# firstProject_1_1.net
KiCad netlist of a schematic drawn in EAGLE
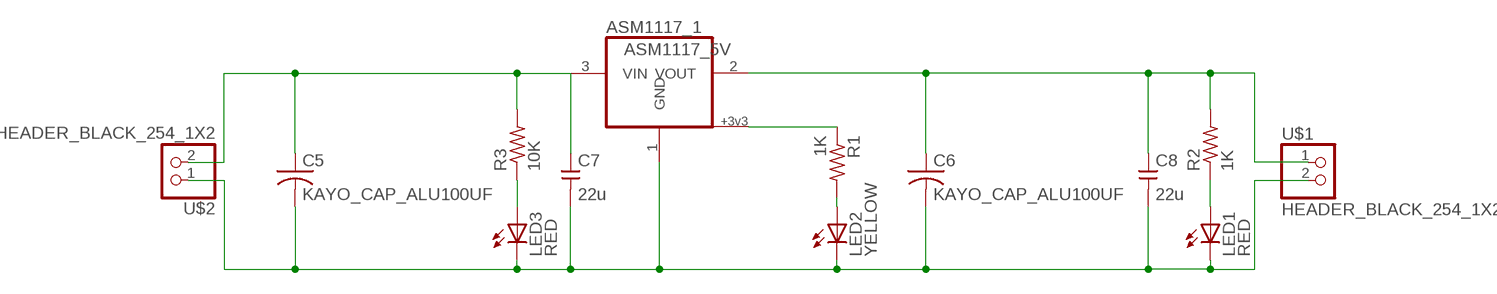
[diagram p0: schematic, sheet 1]

(export (version "E")
  (design (tool "Eeschema 10.0.6"))
  (components
    (comp (ref "ASM1117_1")
      (value "ASM1117_5V")
      (footprint "eagle-import:SOT223")
      (fields (field (name "MPN") "REG1117"))
      (libsource (lib "eagle-import") (part "KAYO_REG1117_SOT223_ASM1117_5V"))
    )
    (comp (ref "C5")
      (value "KAYO_CAP_ALU100UF")
      (footprint "eagle-import:RCL_PANASONIC_D")
      (libsource (lib "eagle-import") (part "KAYO_CAP_ALU100UF"))
    )
    (comp (ref "C6")
      (value "KAYO_CAP_ALU100UF")
      (footprint "eagle-import:RCL_PANASONIC_D")
      (libsource (lib "eagle-import") (part "KAYO_CAP_ALU100UF"))
    )
    (comp (ref "C7")
      (value "22u")
      (footprint "eagle-import:KXN_C0603")
      (libsource (lib "eagle-import") (part "KAYO_CAP_CERAMIC_KXN_060322UF"))
    )
    (comp (ref "C8")
      (value "22u")
      (footprint "eagle-import:KXN_C0603")
      (libsource (lib "eagle-import") (part "KAYO_CAP_CERAMIC_KXN_060322UF"))
    )
    (comp (ref "LED1")
      (value "RED")
      (footprint "eagle-import:KXN_LED_0603")
      (libsource (lib "eagle-import") (part "KAYO_LED_KXN_LED_0603_RED"))
    )
    (comp (ref "LED2")
      (value "YELLOW")
      (footprint "eagle-import:KXN_LED_0603")
      (libsource (lib "eagle-import") (part "KAYO_LED_KXN_LED_0603_YELLOW"))
    )
    (comp (ref "LED3")
      (value "RED")
      (footprint "eagle-import:KXN_LED_0603")
      (libsource (lib "eagle-import") (part "KAYO_LED_KXN_LED_0603_RED"))
    )
    (comp (ref "R1")
      (value "1K")
      (footprint "eagle-import:R0603_KXN")
      (libsource (lib "eagle-import") (part "R-US__R0603_KXN1K"))
    )
    (comp (ref "R2")
      (value "1K")
      (footprint "eagle-import:R0603_KXN")
      (libsource (lib "eagle-import") (part "R-US__R0603_KXN1K"))
    )
    (comp (ref "R3")
      (value "10K")
      (footprint "eagle-import:R0603_KXN")
      (libsource (lib "eagle-import") (part "R-US__R0603_KXN10K"))
    )
    (comp (ref "U$1")
      (value "HEADER_BLACK_254_1X2")
      (footprint "eagle-import:HEADER_1X2_254")
      (libsource (lib "eagle-import") (part "KXN_HEADER_1X2"))
    )
    (comp (ref "U$2")
      (value "HEADER_BLACK_254_1X2")
      (footprint "eagle-import:HEADER_1X2_254")
      (libsource (lib "eagle-import") (part "KXN_HEADER_1X2"))
    )
  )
  (nets
    (net (code "1") (name "Net-(ASM1117_1-GND)") (class "Default")
      (node (ref "ASM1117_1") (pin "1") (pinfunction "GND_1") (pintype "power_in"))
      (node (ref "C5") (pin "-") (pinfunction "2_-") (pintype "passive"))
      (node (ref "C6") (pin "-") (pinfunction "2_-") (pintype "passive"))
      (node (ref "C7") (pin "2") (pinfunction "-_2") (pintype "passive"))
      (node (ref "C8") (pin "2") (pinfunction "-_2") (pintype "passive"))
      (node (ref "LED1") (pin "C") (pinfunction "C_C") (pintype "passive"))
      (node (ref "LED2") (pin "C") (pinfunction "C_C") (pintype "passive"))
      (node (ref "LED3") (pin "C") (pinfunction "C_C") (pintype "passive"))
      (node (ref "U$1") (pin "2") (pinfunction "2_2") (pintype "passive"))
      (node (ref "U$2") (pin "1") (pinfunction "1_1") (pintype "passive"))
    )
    (net (code "2") (name "Net-(ASM1117_1-Pad4)") (class "Default")
      (node (ref "ASM1117_1") (pin "4") (pinfunction "4_4") (pintype "bidirectional"))
      (node (ref "R1") (pin "1") (pinfunction "1_1") (pintype "passive"))
    )
    (net (code "3") (name "Net-(ASM1117_1-VIN)") (class "Default")
      (node (ref "ASM1117_1") (pin "3") (pinfunction "VIN_3") (pintype "input"))
      (node (ref "C5") (pin "+") (pinfunction "1_+") (pintype "passive"))
      (node (ref "C7") (pin "1") (pinfunction "+_1") (pintype "passive"))
      (node (ref "R3") (pin "2") (pinfunction "2_2") (pintype "passive"))
      (node (ref "U$2") (pin "2") (pinfunction "2_2") (pintype "passive"))
    )
    (net (code "4") (name "Net-(ASM1117_1-VOUT)") (class "Default")
      (node (ref "ASM1117_1") (pin "2") (pinfunction "VOUT_2") (pintype "output"))
      (node (ref "C6") (pin "+") (pinfunction "1_+") (pintype "passive"))
      (node (ref "C8") (pin "1") (pinfunction "+_1") (pintype "passive"))
      (node (ref "R2") (pin "2") (pinfunction "2_2") (pintype "passive"))
      (node (ref "U$1") (pin "1") (pinfunction "1_1") (pintype "passive"))
    )
    (net (code "5") (name "Net-(LED1-PadA)") (class "Default")
      (node (ref "LED1") (pin "A") (pinfunction "A_A") (pintype "passive"))
      (node (ref "R2") (pin "1") (pinfunction "1_1") (pintype "passive"))
    )
    (net (code "6") (name "Net-(LED2-PadA)") (class "Default")
      (node (ref "LED2") (pin "A") (pinfunction "A_A") (pintype "passive"))
      (node (ref "R1") (pin "2") (pinfunction "2_2") (pintype "passive"))
    )
    (net (code "7") (name "Net-(LED3-PadA)") (class "Default")
      (node (ref "LED3") (pin "A") (pinfunction "A_A") (pintype "passive"))
      (node (ref "R3") (pin "1") (pinfunction "1_1") (pintype "passive"))
    )
  )
)
